# Sheet1.net
KiCad netlist of a schematic drawn in Altium Designer
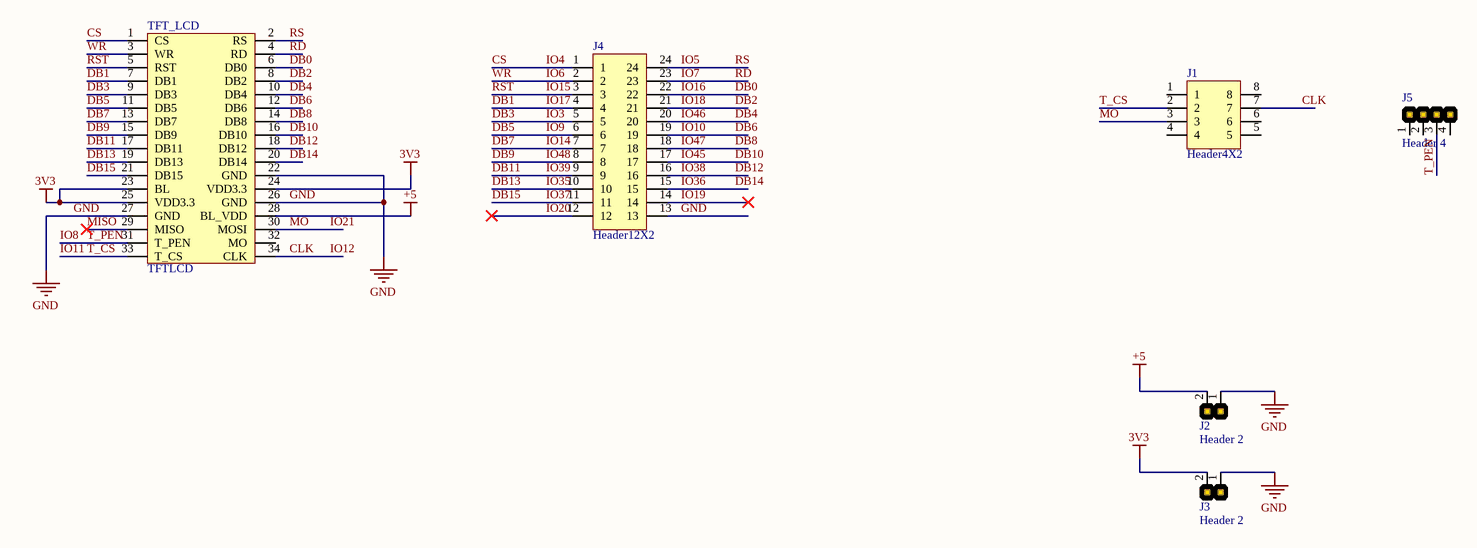
[diagram p0: Sheet1.SchDoc]

(export (version "E")
  (design (tool "Eeschema 10.0.6"))
  (components
    (comp (ref "J1") (value "Header4X2") (footprint "HDR4X2") (libsource (lib "Schlib1") (part "Header4X2")))
    (comp (ref "J2") (value "Header 2") (footprint "HDR2") (libsource (lib "Schlib1") (part "Header 2")))
    (comp (ref "J3") (value "Header 2") (footprint "HDR2") (libsource (lib "Schlib1") (part "Header 2")))
    (comp (ref "J4")
      (value "Header12X2")
      (footprint "HDR12X2_Female")
      (libsource (lib "Schlib1") (part "Header12X2"))
    )
    (comp (ref "J5") (value "Header 4") (footprint "HDR4") (libsource (lib "Schlib1") (part "Header 4")))
    (comp (ref "TFT_LCD")
      (value "TFTLCD")
      (footprint "TFTLCD-4.3")
      (description "正点原子MCU屏通用接口")
      (libsource (lib "Schlib1") (part "TFTLCD"))
    )
  )
  (nets
    (net (code "1") (name "+5") (class "Default")
      (node (ref "J2") (pin "2") (pinfunction "2_2") (pintype "passive"))
      (node (ref "TFT_LCD") (pin "28") (pinfunction "BL_VDD_28") (pintype "passive"))
    )
    (net (code "2") (name "/CLK") (class "Default")
      (node (ref "J1") (pin "7") (pinfunction "7_7") (pintype "passive"))
      (node (ref "TFT_LCD") (pin "34") (pinfunction "CLK_34") (pintype "passive"))
    )
    (net (code "3") (name "/CS") (class "Default")
      (node (ref "J4") (pin "1") (pinfunction "1_1") (pintype "passive"))
      (node (ref "TFT_LCD") (pin "1") (pinfunction "CS_1") (pintype "passive"))
    )
    (net (code "4") (name "/DB0") (class "Default")
      (node (ref "J4") (pin "22") (pinfunction "22_22") (pintype "passive"))
      (node (ref "TFT_LCD") (pin "6") (pinfunction "DB0_6") (pintype "passive"))
    )
    (net (code "5") (name "/DB1") (class "Default")
      (node (ref "J4") (pin "4") (pinfunction "4_4") (pintype "passive"))
      (node (ref "TFT_LCD") (pin "7") (pinfunction "DB1_7") (pintype "passive"))
    )
    (net (code "6") (name "/DB2") (class "Default")
      (node (ref "J4") (pin "21") (pinfunction "21_21") (pintype "passive"))
      (node (ref "TFT_LCD") (pin "8") (pinfunction "DB2_8") (pintype "passive"))
    )
    (net (code "7") (name "/DB3") (class "Default")
      (node (ref "J4") (pin "5") (pinfunction "5_5") (pintype "passive"))
      (node (ref "TFT_LCD") (pin "9") (pinfunction "DB3_9") (pintype "passive"))
    )
    (net (code "8") (name "/DB4") (class "Default")
      (node (ref "J4") (pin "20") (pinfunction "20_20") (pintype "passive"))
      (node (ref "TFT_LCD") (pin "10") (pinfunction "DB4_10") (pintype "passive"))
    )
    (net (code "9") (name "/DB5") (class "Default")
      (node (ref "J4") (pin "6") (pinfunction "6_6") (pintype "passive"))
      (node (ref "TFT_LCD") (pin "11") (pinfunction "DB5_11") (pintype "passive"))
    )
    (net (code "10") (name "/DB6") (class "Default")
      (node (ref "J4") (pin "19") (pinfunction "19_19") (pintype "passive"))
      (node (ref "TFT_LCD") (pin "12") (pinfunction "DB6_12") (pintype "passive"))
    )
    (net (code "11") (name "/DB7") (class "Default")
      (node (ref "J4") (pin "7") (pinfunction "7_7") (pintype "passive"))
      (node (ref "TFT_LCD") (pin "13") (pinfunction "DB7_13") (pintype "passive"))
    )
    (net (code "12") (name "/DB8") (class "Default")
      (node (ref "J4") (pin "18") (pinfunction "18_18") (pintype "passive"))
      (node (ref "TFT_LCD") (pin "14") (pinfunction "DB8_14") (pintype "passive"))
    )
    (net (code "13") (name "/DB9") (class "Default")
      (node (ref "J4") (pin "8") (pinfunction "8_8") (pintype "passive"))
      (node (ref "TFT_LCD") (pin "15") (pinfunction "DB9_15") (pintype "passive"))
    )
    (net (code "14") (name "/DB10") (class "Default")
      (node (ref "J4") (pin "17") (pinfunction "17_17") (pintype "passive"))
      (node (ref "TFT_LCD") (pin "16") (pinfunction "DB10_16") (pintype "passive"))
    )
    (net (code "15") (name "/DB11") (class "Default")
      (node (ref "J4") (pin "9") (pinfunction "9_9") (pintype "passive"))
      (node (ref "TFT_LCD") (pin "17") (pinfunction "DB11_17") (pintype "passive"))
    )
    (net (code "16") (name "/DB12") (class "Default")
      (node (ref "J4") (pin "16") (pinfunction "16_16") (pintype "passive"))
      (node (ref "TFT_LCD") (pin "18") (pinfunction "DB12_18") (pintype "passive"))
    )
    (net (code "17") (name "/DB13") (class "Default")
      (node (ref "J4") (pin "10") (pinfunction "10_10") (pintype "passive"))
      (node (ref "TFT_LCD") (pin "19") (pinfunction "DB13_19") (pintype "passive"))
    )
    (net (code "18") (name "/DB14") (class "Default")
      (node (ref "J4") (pin "15") (pinfunction "15_15") (pintype "passive"))
      (node (ref "TFT_LCD") (pin "20") (pinfunction "DB14_20") (pintype "passive"))
    )
    (net (code "19") (name "/DB15") (class "Default")
      (node (ref "J4") (pin "11") (pinfunction "11_11") (pintype "passive"))
      (node (ref "TFT_LCD") (pin "21") (pinfunction "DB15_21") (pintype "passive"))
    )
    (net (code "20") (name "/IO5") (class "Default")
      (node (ref "J4") (pin "24") (pinfunction "24_24") (pintype "passive"))
      (node (ref "TFT_LCD") (pin "2") (pinfunction "RS_2") (pintype "passive"))
    )
    (net (code "21") (name "/IO6") (class "Default")
      (node (ref "J4") (pin "2") (pinfunction "2_2") (pintype "passive"))
      (node (ref "TFT_LCD") (pin "3") (pinfunction "WR_3") (pintype "passive"))
    )
    (net (code "22") (name "/IO7") (class "Default")
      (node (ref "J4") (pin "23") (pinfunction "23_23") (pintype "passive"))
      (node (ref "TFT_LCD") (pin "4") (pinfunction "RD_4") (pintype "passive"))
    )
    (net (code "23") (name "/IO8") (class "Default")
      (node (ref "J5") (pin "3") (pinfunction "3_3") (pintype "passive"))
      (node (ref "TFT_LCD") (pin "31") (pinfunction "T_PEN_31") (pintype "passive"))
    )
    (net (code "24") (name "/IO11") (class "Default")
      (node (ref "J1") (pin "2") (pinfunction "2_2") (pintype "passive"))
      (node (ref "TFT_LCD") (pin "33") (pinfunction "T_CS_33") (pintype "passive"))
    )
    (net (code "25") (name "/IO15") (class "Default")
      (node (ref "J4") (pin "3") (pinfunction "3_3") (pintype "passive"))
      (node (ref "TFT_LCD") (pin "5") (pinfunction "RST_5") (pintype "passive"))
    )
    (net (code "26") (name "/IO19") (class "Default")
      (node (ref "J4") (pin "14") (pinfunction "14_14") (pintype "passive+no_connect"))
    )
    (net (code "27") (name "/IO20") (class "Default")
      (node (ref "J4") (pin "12") (pinfunction "12_12") (pintype "passive+no_connect"))
    )
    (net (code "28") (name "/IO21") (class "Default")
      (node (ref "J1") (pin "3") (pinfunction "3_3") (pintype "passive"))
      (node (ref "TFT_LCD") (pin "30") (pinfunction "MOSI_30") (pintype "passive"))
    )
    (net (code "29") (name "/MISO") (class "Default")
      (node (ref "TFT_LCD") (pin "29") (pinfunction "MISO_29") (pintype "passive+no_connect"))
    )
    (net (code "30") (name "3V3") (class "Default")
      (node (ref "J3") (pin "2") (pinfunction "2_2") (pintype "passive"))
      (node (ref "TFT_LCD") (pin "23") (pinfunction "BL_23") (pintype "passive"))
      (node (ref "TFT_LCD") (pin "24") (pinfunction "VDD3.3_24") (pintype "passive"))
      (node (ref "TFT_LCD") (pin "25") (pinfunction "VDD3.3_25") (pintype "passive"))
    )
    (net (code "31") (name "GND") (class "Default")
      (node (ref "J2") (pin "1") (pinfunction "1_1") (pintype "passive"))
      (node (ref "J3") (pin "1") (pinfunction "1_1") (pintype "passive"))
      (node (ref "J4") (pin "13") (pinfunction "13_13") (pintype "passive"))
      (node (ref "TFT_LCD") (pin "22") (pinfunction "GND_22") (pintype "passive"))
      (node (ref "TFT_LCD") (pin "26") (pinfunction "GND_26") (pintype "passive"))
      (node (ref "TFT_LCD") (pin "27") (pinfunction "GND_27") (pintype "passive"))
    )
    (net (code "32") (name "unconnected-(J1-Pad1)") (class "Default")
      (node (ref "J1") (pin "1") (pinfunction "1_1") (pintype "passive"))
    )
    (net (code "33") (name "unconnected-(J1-Pad4)") (class "Default")
      (node (ref "J1") (pin "4") (pinfunction "4_4") (pintype "passive"))
    )
    (net (code "34") (name "unconnected-(J1-Pad5)") (class "Default")
      (node (ref "J1") (pin "5") (pinfunction "5_5") (pintype "passive"))
    )
    (net (code "35") (name "unconnected-(J1-Pad6)") (class "Default")
      (node (ref "J1") (pin "6") (pinfunction "6_6") (pintype "passive"))
    )
    (net (code "36") (name "unconnected-(J1-Pad8)") (class "Default")
      (node (ref "J1") (pin "8") (pinfunction "8_8") (pintype "passive"))
    )
    (net (code "37") (name "unconnected-(J5-Pad1)") (class "Default")
      (node (ref "J5") (pin "1") (pinfunction "1_1") (pintype "passive"))
    )
    (net (code "38") (name "unconnected-(J5-Pad2)") (class "Default")
      (node (ref "J5") (pin "2") (pinfunction "2_2") (pintype "passive"))
    )
    (net (code "39") (name "unconnected-(J5-Pad4)") (class "Default")
      (node (ref "J5") (pin "4") (pinfunction "4_4") (pintype "passive"))
    )
    (net (code "40") (name "unconnected-(TFT_LCD-MO-Pad32)") (class "Default")
      (node (ref "TFT_LCD") (pin "32") (pinfunction "MO_32") (pintype "passive"))
    )
  )
)
